# Meanwell_FE.net
KiCad netlist of a schematic drawn in EAGLE
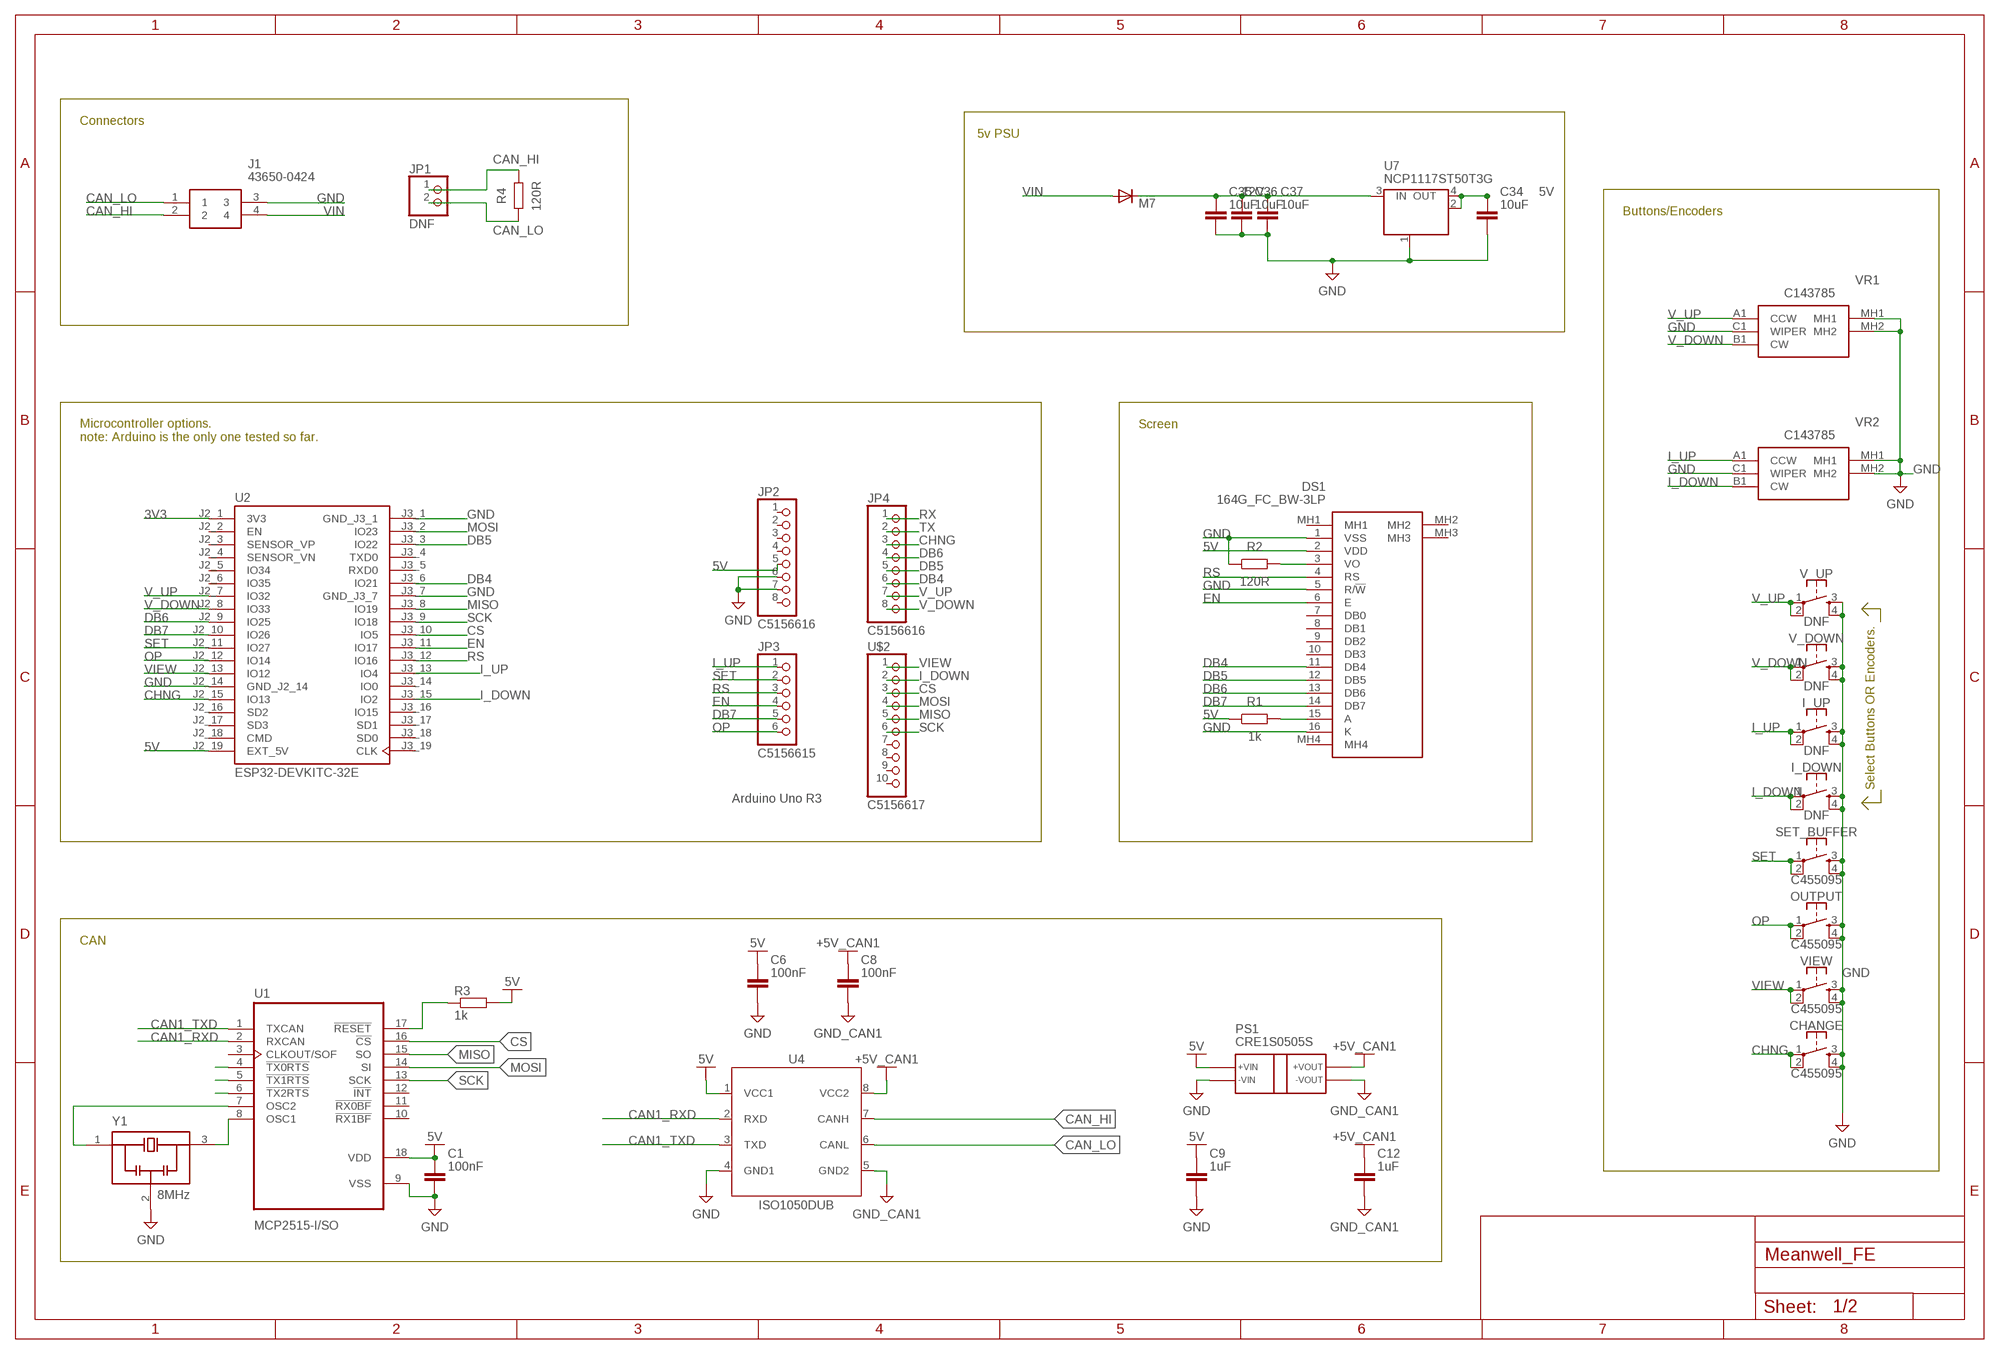
[diagram p0: schematic, sheet 1]
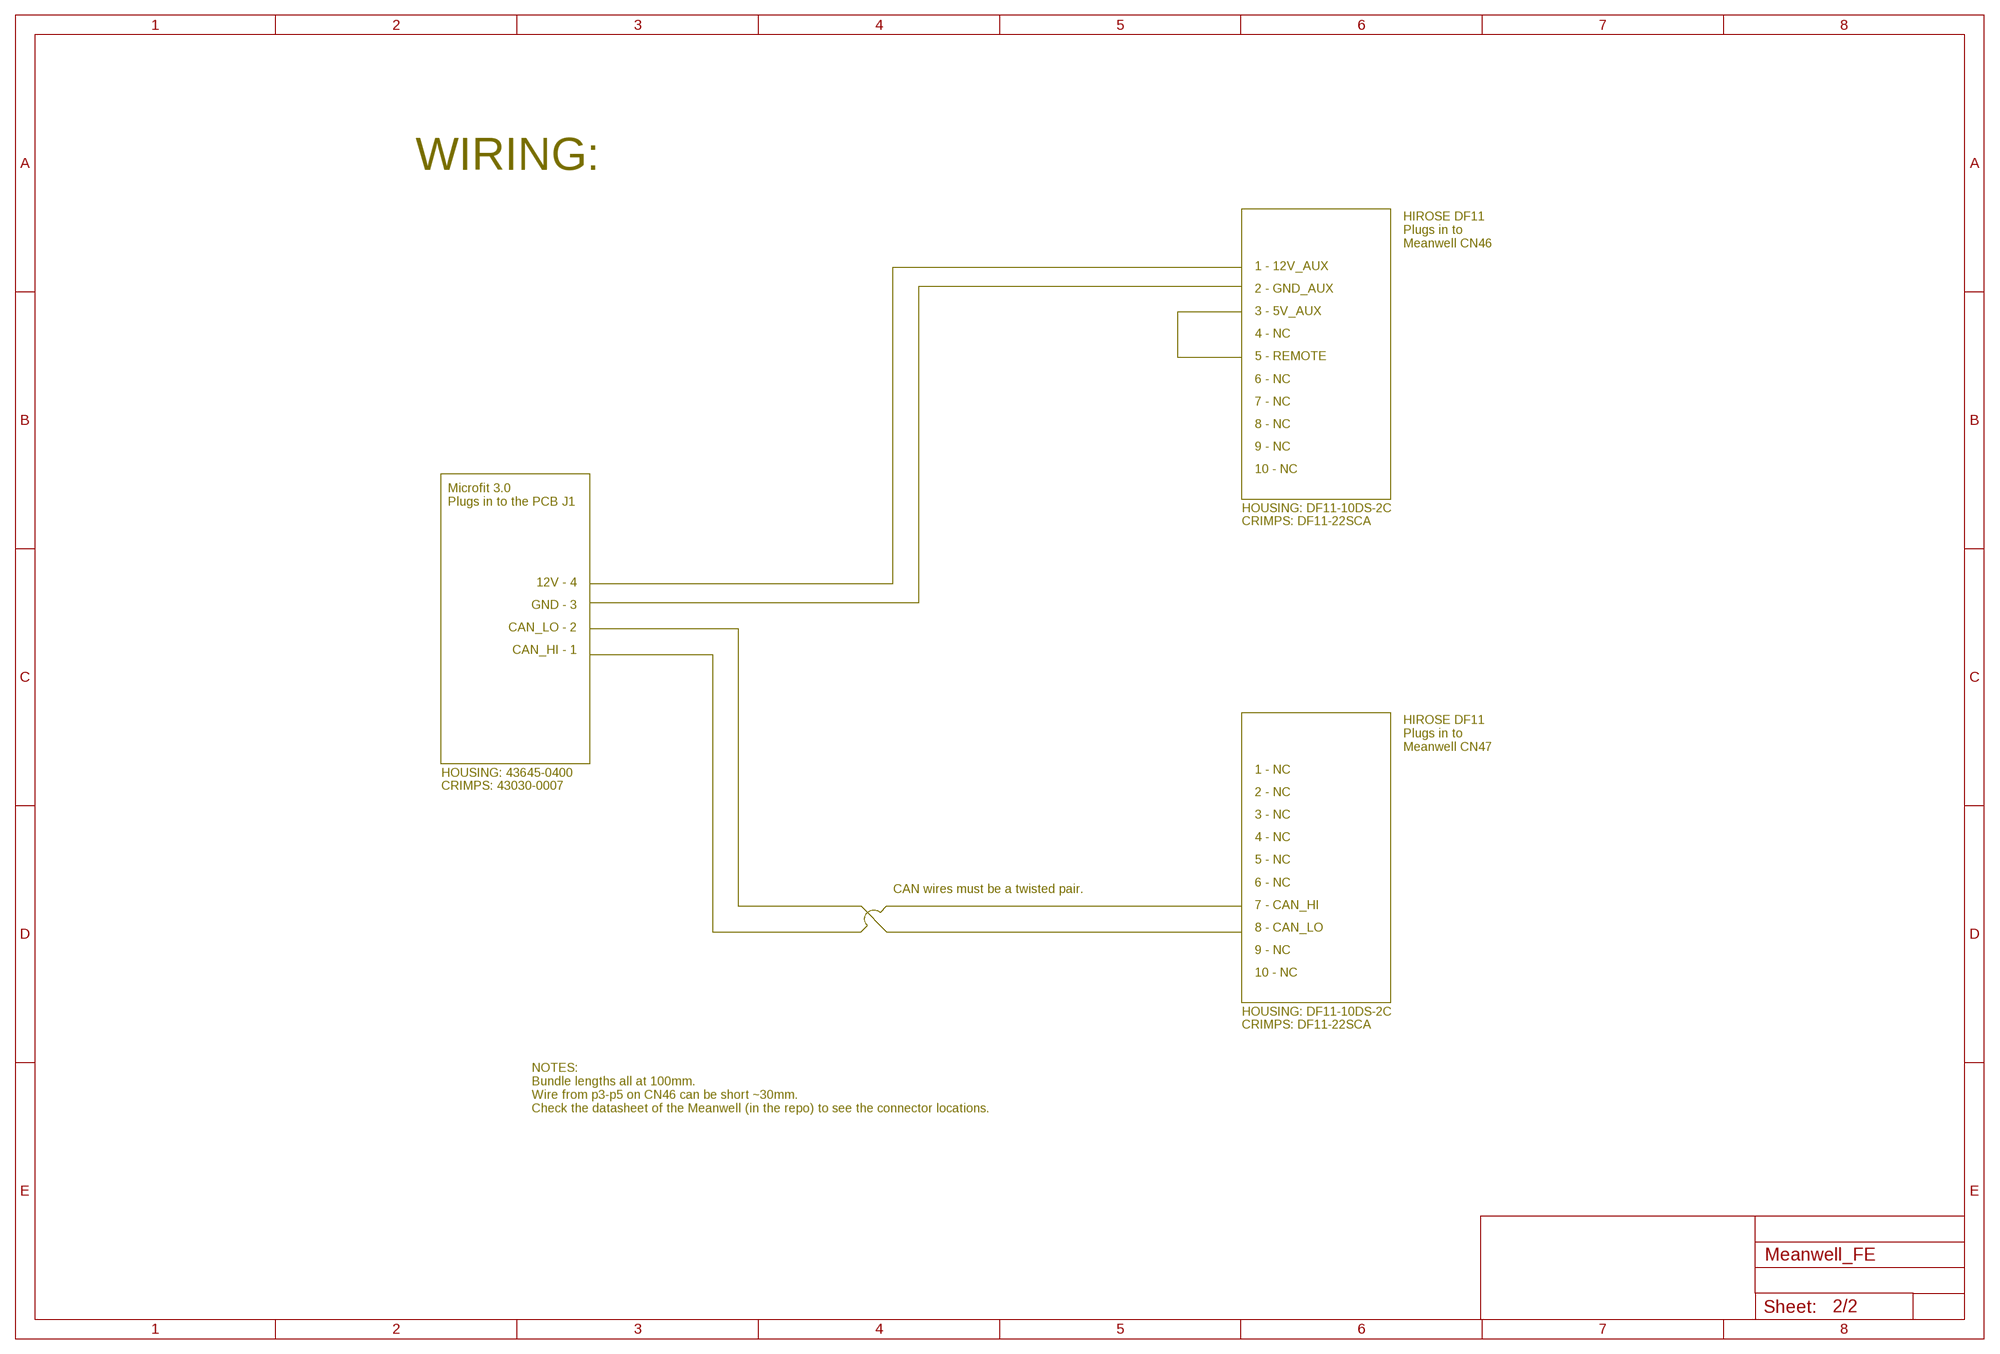
[diagram p1: schematic, sheet 2]

(export (version "E")
  (design (tool "Eeschema 10.0.6"))
  (components
    (comp (ref "C1")
      (value "100nF")
      (footprint "eagle-import:CAPC1608X85")
      (libsource (lib "eagle-import") (part "CCHIP-0603(1608-METRIC)_"))
    )
    (comp (ref "C6")
      (value "100nF")
      (footprint "eagle-import:CAPC1608X85")
      (libsource (lib "eagle-import") (part "CCHIP-0603(1608-METRIC)_"))
    )
    (comp (ref "C8")
      (value "100nF")
      (footprint "eagle-import:CAPC1608X85")
      (libsource (lib "eagle-import") (part "CCHIP-0603(1608-METRIC)_"))
    )
    (comp (ref "C9")
      (value "1uF")
      (footprint "eagle-import:CAPC1608X85")
      (libsource (lib "eagle-import") (part "CCHIP-0603(1608-METRIC)_"))
    )
    (comp (ref "C12")
      (value "1uF")
      (footprint "eagle-import:CAPC1608X85")
      (libsource (lib "eagle-import") (part "CCHIP-0603(1608-METRIC)_"))
    )
    (comp (ref "C34")
      (value "10uF")
      (footprint "eagle-import:CAPC2012X110")
      (libsource (lib "eagle-import") (part "CCHIP-0805(2012-METRIC)_"))
    )
    (comp (ref "C35")
      (value "10uF")
      (footprint "eagle-import:CAPC2012X110")
      (libsource (lib "eagle-import") (part "CCHIP-0805(2012-METRIC)_"))
    )
    (comp (ref "C36")
      (value "10uF")
      (footprint "eagle-import:CAPC2012X110")
      (libsource (lib "eagle-import") (part "CCHIP-0805(2012-METRIC)_"))
    )
    (comp (ref "C37")
      (value "10uF")
      (footprint "eagle-import:CAPC2012X110")
      (libsource (lib "eagle-import") (part "CCHIP-0805(2012-METRIC)_"))
    )
    (comp (ref "CHANGE")
      (value "C455095")
      (footprint "eagle-import:SWITCH-MOMENTARY-PTH-6.5MM")
      (libsource (lib "eagle-import") (part "SWITCH_MOMENTARY"))
    )
    (comp (ref "D1")
      (value "M7")
      (footprint "eagle-import:SMB")
      (libsource (lib "eagle-import") (part "DIODE-SMB"))
    )
    (comp (ref "DS1")
      (value "164G_FC_BW-3LP")
      (footprint "eagle-import:164GFCBW3LP")
      (fields (field (name "MANUFACTURER_PART_NUMBER") "164G FC BW-3LP"))
      (libsource (lib "eagle-import") (part "164G_FC_BW-3LP"))
    )
    (comp (ref "I_DOWN")
      (value "DNF")
      (footprint "eagle-import:SWITCH-MOMENTARY-PTH-6.5MM")
      (libsource (lib "eagle-import") (part "SWITCH_MOMENTARY"))
    )
    (comp (ref "I_UP")
      (value "DNF")
      (footprint "eagle-import:SWITCH-MOMENTARY-PTH-6.5MM")
      (libsource (lib "eagle-import") (part "SWITCH_MOMENTARY"))
    )
    (comp (ref "J1")
      (value "43650-0424")
      (footprint "eagle-import:43650-04YY_242526")
      (fields (field (name "MOUSER_PART_NUMBER") "538-43650-0424"))
      (libsource (lib "eagle-import") (part "43650-0424"))
    )
    (comp (ref "JP1")
      (value "DNF")
      (footprint "eagle-import:1X02")
      (libsource (lib "eagle-import") (part "PINHD-1X2"))
    )
    (comp (ref "JP2")
      (value "C5156616")
      (footprint "eagle-import:1X08-BIG")
      (libsource (lib "eagle-import") (part "PINHD-1X8BIG"))
    )
    (comp (ref "JP3")
      (value "C5156615")
      (footprint "eagle-import:1X06-BIG")
      (libsource (lib "eagle-import") (part "PINHD-1X6B"))
    )
    (comp (ref "JP4")
      (value "C5156616")
      (footprint "eagle-import:1X08-BIG")
      (libsource (lib "eagle-import") (part "PINHD-1X8BIG"))
    )
    (comp (ref "OUTPUT")
      (value "C455095")
      (footprint "eagle-import:SWITCH-MOMENTARY-PTH-6.5MM")
      (libsource (lib "eagle-import") (part "SWITCH_MOMENTARY"))
    )
    (comp (ref "PS1")
      (value "CRE1S0505S")
      (footprint "eagle-import:CRE1(SC)")
      (fields
        (field (name "MANUFACTURER_PART_NUMBER") "CRE1S2405SC")
        (field (name "MOUSER_PART_NUMBER") "580-CRE1S2405SC")
      )
      (libsource (lib "eagle-import") (part "CRE1S0505S"))
    )
    (comp (ref "R1")
      (value "1k")
      (footprint "eagle-import:RESC1608X60")
      (libsource (lib "eagle-import") (part "RCHIP-0603(1608-METRIC)_"))
    )
    (comp (ref "R2")
      (value "120R")
      (footprint "eagle-import:RESC1608X60")
      (libsource (lib "eagle-import") (part "RCHIP-0603(1608-METRIC)_"))
    )
    (comp (ref "R3")
      (value "1k")
      (footprint "eagle-import:RESC1608X60")
      (libsource (lib "eagle-import") (part "RCHIP-0603(1608-METRIC)_"))
    )
    (comp (ref "R4")
      (value "120R")
      (footprint "eagle-import:RESC1608X60")
      (libsource (lib "eagle-import") (part "RCHIP-0603(1608-METRIC)_"))
    )
    (comp (ref "SET_BUFFER")
      (value "C455095")
      (footprint "eagle-import:SWITCH-MOMENTARY-PTH-6.5MM")
      (libsource (lib "eagle-import") (part "SWITCH_MOMENTARY"))
    )
    (comp (ref "U$2")
      (value "C5156617")
      (footprint "eagle-import:1X10-BIG")
      (libsource (lib "eagle-import") (part "PINHD-1X10"))
    )
    (comp (ref "U1")
      (value "MCP2515-I/SO")
      (footprint "eagle-import:SOIC127P1030X265-18N")
      (fields (field (name "MF") "Microchip"))
      (libsource (lib "eagle-import") (part "MCP2515-I/SO"))
    )
    (comp (ref "U2")
      (value "ESP32-DEVKITC-32E")
      (footprint "eagle-import:MODULE_ESP32-DEVKITC-32E")
      (fields (field (name "MANUFACTURER") "Espressif Systems"))
      (libsource (lib "eagle-import") (part "ESP32-DEVKITC-32E"))
    )
    (comp (ref "U4")
      (value "ISO1050DUB")
      (footprint "eagle-import:SOP254P1040X485-8")
      (fields (field (name "MANUFACTURER") "Texas Instruments"))
      (libsource (lib "eagle-import") (part "ISO1050DUB"))
    )
    (comp (ref "U7")
      (value "NCP1117ST50T3G")
      (footprint "eagle-import:SOT223")
      (libsource (lib "eagle-import") (part "MC33269ST-3.3T3"))
    )
    (comp (ref "VIEW")
      (value "C455095")
      (footprint "eagle-import:SWITCH-MOMENTARY-PTH-6.5MM")
      (libsource (lib "eagle-import") (part "SWITCH_MOMENTARY"))
    )
    (comp (ref "VR1")
      (value "C143785")
      (footprint "eagle-import:PEC12R4215FN0024")
      (fields
        (field (name "MANUFACTURER_PART_NUMBER") "PEC12R-4215F-N0024")
        (field (name "MOUSER_PART_NUMBER") "652-PEC12R4215FN0024")
      )
      (libsource (lib "eagle-import") (part "PEC12R-4215F-N0024"))
    )
    (comp (ref "VR2")
      (value "C143785")
      (footprint "eagle-import:PEC12R4215FN0024")
      (fields
        (field (name "MANUFACTURER_PART_NUMBER") "PEC12R-4215F-N0024")
        (field (name "MOUSER_PART_NUMBER") "652-PEC12R4215FN0024")
      )
      (libsource (lib "eagle-import") (part "PEC12R-4215F-N0024"))
    )
    (comp (ref "V_DOWN")
      (value "DNF")
      (footprint "eagle-import:SWITCH-MOMENTARY-PTH-6.5MM")
      (libsource (lib "eagle-import") (part "SWITCH_MOMENTARY"))
    )
    (comp (ref "V_UP")
      (value "DNF")
      (footprint "eagle-import:SWITCH-MOMENTARY-PTH-6.5MM")
      (libsource (lib "eagle-import") (part "SWITCH_MOMENTARY"))
    )
    (comp (ref "Y1")
      (value "8MHz")
      (footprint "eagle-import:OSC_CSTNE8M00GH5C000R0")
      (fields (field (name "MF") "Murata Electronics") (field (name "MP") "CSTNE8M00GH5C000R0"))
      (libsource (lib "eagle-import") (part "CSTNE8M00GH5C000R0"))
    )
  )
  (nets
    (net (code "1") (name "+5V_CAN1") (class "Default")
      (node (ref "C12") (pin "1") (pinfunction "1_1") (pintype "passive"))
      (node (ref "C8") (pin "1") (pinfunction "1_1") (pintype "passive"))
      (node (ref "PS1") (pin "4") (pinfunction "+VOUT_4") (pintype "bidirectional"))
      (node (ref "U4") (pin "8") (pinfunction "VCC2_8") (pintype "power_in"))
    )
    (net (code "2") (name "3V3") (class "Default")
      (node (ref "U2") (pin "J2_1") (pinfunction "3V3_J2_1") (pintype "power_in"))
    )
    (net (code "3") (name "5V") (class "Default")
      (node (ref "C1") (pin "1") (pinfunction "1_1") (pintype "passive"))
      (node (ref "C34") (pin "1") (pinfunction "1_1") (pintype "passive"))
      (node (ref "C6") (pin "1") (pinfunction "1_1") (pintype "passive"))
      (node (ref "C9") (pin "1") (pinfunction "1_1") (pintype "passive"))
      (node (ref "DS1") (pin "2") (pinfunction "VDD_2") (pintype "bidirectional"))
      (node (ref "JP2") (pin "5") (pinfunction "5_5") (pintype "passive"))
      (node (ref "PS1") (pin "2") (pinfunction "+VIN_2") (pintype "bidirectional"))
      (node (ref "R1") (pin "1") (pinfunction "1_1") (pintype "passive"))
      (node (ref "R3") (pin "2") (pinfunction "2_2") (pintype "passive"))
      (node (ref "U1") (pin "18") (pinfunction "VDD_18") (pintype "power_in"))
      (node (ref "U2") (pin "J2_19") (pinfunction "EXT_5V_J2_19") (pintype "power_in"))
      (node (ref "U4") (pin "1") (pinfunction "VCC1_1") (pintype "power_in"))
      (node (ref "U7") (pin "2") (pinfunction "OUT_2") (pintype "passive"))
      (node (ref "U7") (pin "4") (pinfunction "OUT_4") (pintype "passive"))
    )
    (net (code "4") (name "12V") (class "Default")
      (node (ref "C35") (pin "1") (pinfunction "1_1") (pintype "passive"))
      (node (ref "C36") (pin "1") (pinfunction "1_1") (pintype "passive"))
      (node (ref "C37") (pin "1") (pinfunction "1_1") (pintype "passive"))
      (node (ref "D1") (pin "C") (pinfunction "C_C") (pintype "passive"))
      (node (ref "U7") (pin "3") (pinfunction "IN_3") (pintype "input"))
    )
    (net (code "5") (name "CAN1_RXD") (class "Default")
      (node (ref "U1") (pin "2") (pinfunction "RXCAN_2") (pintype "input"))
      (node (ref "U4") (pin "2") (pinfunction "RXD_2") (pintype "output"))
    )
    (net (code "6") (name "CAN1_TXD") (class "Default")
      (node (ref "U1") (pin "1") (pinfunction "TXCAN_1") (pintype "output"))
      (node (ref "U4") (pin "3") (pinfunction "TXD_3") (pintype "input"))
    )
    (net (code "7") (name "CAN_HI") (class "Default")
      (node (ref "J1") (pin "2") (pinfunction "2_2") (pintype "bidirectional"))
      (node (ref "JP1") (pin "1") (pinfunction "1_1") (pintype "passive"))
      (node (ref "R4") (pin "2") (pinfunction "2_2") (pintype "passive"))
      (node (ref "U4") (pin "7") (pinfunction "CANH_7") (pintype "bidirectional"))
    )
    (net (code "8") (name "CAN_LO") (class "Default")
      (node (ref "J1") (pin "1") (pinfunction "1_1") (pintype "bidirectional"))
      (node (ref "JP1") (pin "2") (pinfunction "2_2") (pintype "passive"))
      (node (ref "R4") (pin "1") (pinfunction "1_1") (pintype "passive"))
      (node (ref "U4") (pin "6") (pinfunction "CANL_6") (pintype "bidirectional"))
    )
    (net (code "9") (name "CHNG") (class "Default")
      (node (ref "CHANGE") (pin "1") (pinfunction "1_1") (pintype "passive"))
      (node (ref "CHANGE") (pin "2") (pinfunction "2_2") (pintype "passive"))
      (node (ref "JP4") (pin "3") (pinfunction "3_3") (pintype "passive"))
      (node (ref "U2") (pin "J2_15") (pinfunction "IO13_J2_15") (pintype "bidirectional"))
    )
    (net (code "10") (name "CS") (class "Default")
      (node (ref "U$2") (pin "3") (pinfunction "3_3") (pintype "passive"))
      (node (ref "U1") (pin "16") (pinfunction "~{CS}_16") (pintype "input"))
      (node (ref "U2") (pin "J3_10") (pinfunction "IO5_J3_10") (pintype "bidirectional"))
    )
    (net (code "11") (name "DB4") (class "Default")
      (node (ref "DS1") (pin "11") (pinfunction "DB4_11") (pintype "bidirectional"))
      (node (ref "JP4") (pin "6") (pinfunction "6_6") (pintype "passive"))
      (node (ref "U2") (pin "J3_6") (pinfunction "IO21_J3_6") (pintype "bidirectional"))
    )
    (net (code "12") (name "DB5") (class "Default")
      (node (ref "DS1") (pin "12") (pinfunction "DB5_12") (pintype "bidirectional"))
      (node (ref "JP4") (pin "5") (pinfunction "5_5") (pintype "passive"))
      (node (ref "U2") (pin "J3_3") (pinfunction "IO22_J3_3") (pintype "bidirectional"))
    )
    (net (code "13") (name "DB6") (class "Default")
      (node (ref "DS1") (pin "13") (pinfunction "DB6_13") (pintype "bidirectional"))
      (node (ref "JP4") (pin "4") (pinfunction "4_4") (pintype "passive"))
      (node (ref "U2") (pin "J2_9") (pinfunction "IO25_J2_9") (pintype "bidirectional"))
    )
    (net (code "14") (name "DB7") (class "Default")
      (node (ref "DS1") (pin "14") (pinfunction "DB7_14") (pintype "bidirectional"))
      (node (ref "JP3") (pin "5") (pinfunction "5_5") (pintype "passive"))
      (node (ref "U2") (pin "J2_10") (pinfunction "IO26_J2_10") (pintype "bidirectional"))
    )
    (net (code "15") (name "EN") (class "Default")
      (node (ref "DS1") (pin "6") (pinfunction "E_6") (pintype "bidirectional"))
      (node (ref "JP3") (pin "4") (pinfunction "4_4") (pintype "passive"))
      (node (ref "U2") (pin "J3_11") (pinfunction "IO17_J3_11") (pintype "bidirectional"))
    )
    (net (code "16") (name "GND") (class "Default")
      (node (ref "C1") (pin "2") (pinfunction "2_2") (pintype "passive"))
      (node (ref "C34") (pin "2") (pinfunction "2_2") (pintype "passive"))
      (node (ref "C35") (pin "2") (pinfunction "2_2") (pintype "passive"))
      (node (ref "C36") (pin "2") (pinfunction "2_2") (pintype "passive"))
      (node (ref "C37") (pin "2") (pinfunction "2_2") (pintype "passive"))
      (node (ref "C6") (pin "2") (pinfunction "2_2") (pintype "passive"))
      (node (ref "C9") (pin "2") (pinfunction "2_2") (pintype "passive"))
      (node (ref "CHANGE") (pin "3") (pinfunction "3_3") (pintype "passive"))
      (node (ref "CHANGE") (pin "4") (pinfunction "4_4") (pintype "passive"))
      (node (ref "DS1") (pin "1") (pinfunction "VSS_1") (pintype "bidirectional"))
      (node (ref "DS1") (pin "16") (pinfunction "K_16") (pintype "bidirectional"))
      (node (ref "DS1") (pin "5") (pinfunction "R/~{W}_5") (pintype "bidirectional"))
      (node (ref "I_DOWN") (pin "3") (pinfunction "3_3") (pintype "passive"))
      (node (ref "I_DOWN") (pin "4") (pinfunction "4_4") (pintype "passive"))
      (node (ref "I_UP") (pin "3") (pinfunction "3_3") (pintype "passive"))
      (node (ref "I_UP") (pin "4") (pinfunction "4_4") (pintype "passive"))
      (node (ref "J1") (pin "3") (pinfunction "3_3") (pintype "bidirectional"))
      (node (ref "JP2") (pin "6") (pinfunction "6_6") (pintype "passive"))
      (node (ref "JP2") (pin "7") (pinfunction "7_7") (pintype "passive"))
      (node (ref "OUTPUT") (pin "3") (pinfunction "3_3") (pintype "passive"))
      (node (ref "OUTPUT") (pin "4") (pinfunction "4_4") (pintype "passive"))
      (node (ref "PS1") (pin "1") (pinfunction "-VIN_1") (pintype "bidirectional"))
      (node (ref "R2") (pin "1") (pinfunction "1_1") (pintype "passive"))
      (node (ref "SET_BUFFER") (pin "3") (pinfunction "3_3") (pintype "passive"))
      (node (ref "SET_BUFFER") (pin "4") (pinfunction "4_4") (pintype "passive"))
      (node (ref "U1") (pin "9") (pinfunction "VSS_9") (pintype "power_in"))
      (node (ref "U2") (pin "J2_14") (pinfunction "GND_J2_14_J2_14") (pintype "power_in"))
      (node (ref "U2") (pin "J3_1") (pinfunction "GND_J3_1_J3_1") (pintype "power_in"))
      (node (ref "U2") (pin "J3_7") (pinfunction "GND_J3_7_J3_7") (pintype "power_in"))
      (node (ref "U4") (pin "4") (pinfunction "GND1_4") (pintype "power_in"))
      (node (ref "U7") (pin "1") (pinfunction "GND/ADJ_1") (pintype "input"))
      (node (ref "VIEW") (pin "3") (pinfunction "3_3") (pintype "passive"))
      (node (ref "VIEW") (pin "4") (pinfunction "4_4") (pintype "passive"))
      (node (ref "VR1") (pin "C1") (pinfunction "WIPER_C1") (pintype "bidirectional"))
      (node (ref "VR1") (pin "MH1") (pinfunction "MH1_MH1") (pintype "bidirectional"))
      (node (ref "VR1") (pin "MH2") (pinfunction "MH2_MH2") (pintype "bidirectional"))
      (node (ref "VR2") (pin "C1") (pinfunction "WIPER_C1") (pintype "bidirectional"))
      (node (ref "VR2") (pin "MH1") (pinfunction "MH1_MH1") (pintype "bidirectional"))
      (node (ref "VR2") (pin "MH2") (pinfunction "MH2_MH2") (pintype "bidirectional"))
      (node (ref "V_DOWN") (pin "3") (pinfunction "3_3") (pintype "passive"))
      (node (ref "V_DOWN") (pin "4") (pinfunction "4_4") (pintype "passive"))
      (node (ref "V_UP") (pin "3") (pinfunction "3_3") (pintype "passive"))
      (node (ref "V_UP") (pin "4") (pinfunction "4_4") (pintype "passive"))
      (node (ref "Y1") (pin "2") (pinfunction "GND_2") (pintype "power_in"))
    )
    (net (code "17") (name "GND_CAN1") (class "Default")
      (node (ref "C12") (pin "2") (pinfunction "2_2") (pintype "passive"))
      (node (ref "C8") (pin "2") (pinfunction "2_2") (pintype "passive"))
      (node (ref "PS1") (pin "3") (pinfunction "-VOUT_3") (pintype "bidirectional"))
      (node (ref "U4") (pin "5") (pinfunction "GND2_5") (pintype "power_in"))
    )
    (net (code "18") (name "I_DOWN") (class "Default")
      (node (ref "I_DOWN") (pin "1") (pinfunction "1_1") (pintype "passive"))
      (node (ref "I_DOWN") (pin "2") (pinfunction "2_2") (pintype "passive"))
      (node (ref "U$2") (pin "2") (pinfunction "2_2") (pintype "passive"))
      (node (ref "U2") (pin "J3_15") (pinfunction "IO2_J3_15") (pintype "bidirectional"))
      (node (ref "VR2") (pin "B1") (pinfunction "CW_B1") (pintype "bidirectional"))
    )
    (net (code "19") (name "I_UP") (class "Default")
      (node (ref "I_UP") (pin "1") (pinfunction "1_1") (pintype "passive"))
      (node (ref "I_UP") (pin "2") (pinfunction "2_2") (pintype "passive"))
      (node (ref "JP3") (pin "1") (pinfunction "1_1") (pintype "passive"))
      (node (ref "U2") (pin "J3_13") (pinfunction "IO4_J3_13") (pintype "bidirectional"))
      (node (ref "VR2") (pin "A1") (pinfunction "CCW_A1") (pintype "bidirectional"))
    )
    (net (code "20") (name "MISO") (class "Default")
      (node (ref "U$2") (pin "5") (pinfunction "5_5") (pintype "passive"))
      (node (ref "U1") (pin "15") (pinfunction "SO_15") (pintype "output"))
      (node (ref "U2") (pin "J3_8") (pinfunction "IO19_J3_8") (pintype "bidirectional"))
    )
    (net (code "21") (name "MOSI") (class "Default")
      (node (ref "U$2") (pin "4") (pinfunction "4_4") (pintype "passive"))
      (node (ref "U1") (pin "14") (pinfunction "SI_14") (pintype "input"))
      (node (ref "U2") (pin "J3_2") (pinfunction "IO23_J3_2") (pintype "bidirectional"))
    )
    (net (code "22") (name "Net-(DS1-A)") (class "Default")
      (node (ref "DS1") (pin "15") (pinfunction "A_15") (pintype "bidirectional"))
      (node (ref "R1") (pin "2") (pinfunction "2_2") (pintype "passive"))
    )
    (net (code "23") (name "Net-(DS1-VO)") (class "Default")
      (node (ref "DS1") (pin "3") (pinfunction "VO_3") (pintype "bidirectional"))
      (node (ref "R2") (pin "2") (pinfunction "2_2") (pintype "passive"))
    )
    (net (code "24") (name "Net-(U1-OSC1)") (class "Default")
      (node (ref "U1") (pin "8") (pinfunction "OSC1_8") (pintype "input"))
      (node (ref "Y1") (pin "3") (pinfunction "OUT_3") (pintype "output"))
    )
    (net (code "25") (name "Net-(U1-OSC2)") (class "Default")
      (node (ref "U1") (pin "7") (pinfunction "OSC2_7") (pintype "output"))
      (node (ref "Y1") (pin "1") (pinfunction "IN_1") (pintype "input"))
    )
    (net (code "26") (name "Net-(U1-~{RESET})") (class "Default")
      (node (ref "R3") (pin "1") (pinfunction "1_1") (pintype "passive"))
      (node (ref "U1") (pin "17") (pinfunction "~{RESET}_17") (pintype "input"))
    )
    (net (code "27") (name "OP") (class "Default")
      (node (ref "JP3") (pin "6") (pinfunction "6_6") (pintype "passive"))
      (node (ref "OUTPUT") (pin "1") (pinfunction "1_1") (pintype "passive"))
      (node (ref "OUTPUT") (pin "2") (pinfunction "2_2") (pintype "passive"))
      (node (ref "U2") (pin "J2_12") (pinfunction "IO14_J2_12") (pintype "bidirectional"))
    )
    (net (code "28") (name "RS") (class "Default")
      (node (ref "DS1") (pin "4") (pinfunction "RS_4") (pintype "bidirectional"))
      (node (ref "JP3") (pin "3") (pinfunction "3_3") (pintype "passive"))
      (node (ref "U2") (pin "J3_12") (pinfunction "IO16_J3_12") (pintype "bidirectional"))
    )
    (net (code "29") (name "RX") (class "Default")
      (node (ref "JP4") (pin "1") (pinfunction "1_1") (pintype "passive"))
    )
    (net (code "30") (name "SCK") (class "Default")
      (node (ref "U$2") (pin "6") (pinfunction "6_6") (pintype "passive"))
      (node (ref "U1") (pin "13") (pinfunction "SCK_13") (pintype "input"))
      (node (ref "U2") (pin "J3_9") (pinfunction "IO18_J3_9") (pintype "bidirectional"))
    )
    (net (code "31") (name "SET") (class "Default")
      (node (ref "JP3") (pin "2") (pinfunction "2_2") (pintype "passive"))
      (node (ref "SET_BUFFER") (pin "1") (pinfunction "1_1") (pintype "passive"))
      (node (ref "SET_BUFFER") (pin "2") (pinfunction "2_2") (pintype "passive"))
      (node (ref "U2") (pin "J2_11") (pinfunction "IO27_J2_11") (pintype "bidirectional"))
    )
    (net (code "32") (name "TX") (class "Default")
      (node (ref "JP4") (pin "2") (pinfunction "2_2") (pintype "passive"))
    )
    (net (code "33") (name "VIEW") (class "Default")
      (node (ref "U$2") (pin "1") (pinfunction "1_1") (pintype "passive"))
      (node (ref "U2") (pin "J2_13") (pinfunction "IO12_J2_13") (pintype "bidirectional"))
      (node (ref "VIEW") (pin "1") (pinfunction "1_1") (pintype "passive"))
      (node (ref "VIEW") (pin "2") (pinfunction "2_2") (pintype "passive"))
    )
    (net (code "34") (name "VIN") (class "Default")
      (node (ref "D1") (pin "A") (pinfunction "A_A") (pintype "passive"))
      (node (ref "J1") (pin "4") (pinfunction "4_4") (pintype "bidirectional"))
    )
    (net (code "35") (name "V_DOWN") (class "Default")
      (node (ref "JP4") (pin "8") (pinfunction "8_8") (pintype "passive"))
      (node (ref "U2") (pin "J2_8") (pinfunction "IO33_J2_8") (pintype "bidirectional"))
      (node (ref "VR1") (pin "B1") (pinfunction "CW_B1") (pintype "bidirectional"))
      (node (ref "V_DOWN") (pin "1") (pinfunction "1_1") (pintype "passive"))
      (node (ref "V_DOWN") (pin "2") (pinfunction "2_2") (pintype "passive"))
    )
    (net (code "36") (name "V_UP") (class "Default")
      (node (ref "JP4") (pin "7") (pinfunction "7_7") (pintype "passive"))
      (node (ref "U2") (pin "J2_7") (pinfunction "IO32_J2_7") (pintype "bidirectional"))
      (node (ref "VR1") (pin "A1") (pinfunction "CCW_A1") (pintype "bidirectional"))
      (node (ref "V_UP") (pin "1") (pinfunction "1_1") (pintype "passive"))
      (node (ref "V_UP") (pin "2") (pinfunction "2_2") (pintype "passive"))
    )
    (net (code "37") (name "unconnected-(DS1-DB0-Pad7)") (class "Default")
      (node (ref "DS1") (pin "7") (pinfunction "DB0_7") (pintype "bidirectional"))
    )
    (net (code "38") (name "unconnected-(DS1-DB1-Pad8)") (class "Default")
      (node (ref "DS1") (pin "8") (pinfunction "DB1_8") (pintype "bidirectional"))
    )
    (net (code "39") (name "unconnected-(DS1-DB2-Pad9)") (class "Default")
      (node (ref "DS1") (pin "9") (pinfunction "DB2_9") (pintype "bidirectional"))
    )
    (net (code "40") (name "unconnected-(DS1-DB3-Pad10)") (class "Default")
      (node (ref "DS1") (pin "10") (pinfunction "DB3_10") (pintype "bidirectional"))
    )
    (net (code "41") (name "unconnected-(DS1-PadMH1)") (class "Default")
      (node (ref "DS1") (pin "MH1") (pinfunction "MH1_MH1") (pintype "bidirectional"))
    )
    (net (code "42") (name "unconnected-(DS1-PadMH2)") (class "Default")
      (node (ref "DS1") (pin "MH2") (pinfunction "MH2_MH2") (pintype "bidirectional"))
    )
    (net (code "43") (name "unconnected-(DS1-PadMH3)") (class "Default")
      (node (ref "DS1") (pin "MH3") (pinfunction "MH3_MH3") (pintype "bidirectional"))
    )
    (net (code "44") (name "unconnected-(DS1-PadMH4)") (class "Default")
      (node (ref "DS1") (pin "MH4") (pinfunction "MH4_MH4") (pintype "bidirectional"))
    )
    (net (code "45") (name "unconnected-(JP2-Pad1)") (class "Default")
      (node (ref "JP2") (pin "1") (pinfunction "1_1") (pintype "passive"))
    )
    (net (code "46") (name "unconnected-(JP2-Pad2)") (class "Default")
      (node (ref "JP2") (pin "2") (pinfunction "2_2") (pintype "passive"))
    )
    (net (code "47") (name "unconnected-(JP2-Pad3)") (class "Default")
      (node (ref "JP2") (pin "3") (pinfunction "3_3") (pintype "passive"))
    )
    (net (code "48") (name "unconnected-(JP2-Pad4)") (class "Default")
      (node (ref "JP2") (pin "4") (pinfunction "4_4") (pintype "passive"))
    )
    (net (code "49") (name "unconnected-(JP2-Pad8)") (class "Default")
      (node (ref "JP2") (pin "8") (pinfunction "8_8") (pintype "passive"))
    )
    (net (code "50") (name "unconnected-(U$2-Pad7)") (class "Default")
      (node (ref "U$2") (pin "7") (pinfunction "7_7") (pintype "passive"))
    )
    (net (code "51") (name "unconnected-(U$2-Pad8)") (class "Default")
      (node (ref "U$2") (pin "8") (pinfunction "8_8") (pintype "passive"))
    )
    (net (code "52") (name "unconnected-(U$2-Pad9)") (class "Default")
      (node (ref "U$2") (pin "9") (pinfunction "9_9") (pintype "passive"))
    )
    (net (code "53") (name "unconnected-(U$2-Pad10)") (class "Default")
      (node (ref "U$2") (pin "10") (pinfunction "10_10") (pintype "passive"))
    )
    (net (code "54") (name "unconnected-(U1-CLKOUT{slash}SOF-Pad3)") (class "Default")
      (node (ref "U1") (pin "3") (pinfunction "CLKOUT/SOF_3") (pintype "output"))
    )
    (net (code "55") (name "unconnected-(U1-~{INT}-Pad12)") (class "Default")
      (node (ref "U1") (pin "12") (pinfunction "~{INT}_12") (pintype "output"))
    )
    (net (code "56") (name "unconnected-(U1-~{RX0BF}-Pad11)") (class "Default")
      (node (ref "U1") (pin "11") (pinfunction "~{RX0BF}_11") (pintype "output"))
    )
    (net (code "57") (name "unconnected-(U1-~{RX1BF}-Pad10)") (class "Default")
      (node (ref "U1") (pin "10") (pinfunction "~{RX1BF}_10") (pintype "output"))
    )
    (net (code "58") (name "unconnected-(U1-~{TX0RTS}-Pad4)") (class "Default")
      (node (ref "U1") (pin "4") (pinfunction "~{TX0RTS}_4") (pintype "bidirectional"))
    )
    (net (code "59") (name "unconnected-(U1-~{TX1RTS}-Pad5)") (class "Default")
      (node (ref "U1") (pin "5") (pinfunction "~{TX1RTS}_5") (pintype "bidirectional"))
    )
    (net (code "60") (name "unconnected-(U1-~{TX2RTS}-Pad6)") (class "Default")
      (node (ref "U1") (pin "6") (pinfunction "~{TX2RTS}_6") (pintype "bidirectional"))
    )
    (net (code "61") (name "unconnected-(U2-CLK-PadJ3_19)") (class "Default")
      (node (ref "U2") (pin "J3_19") (pinfunction "CLK_J3_19") (pintype "bidirectional"))
    )
    (net (code "62") (name "unconnected-(U2-CMD-PadJ2_18)") (class "Default")
      (node (ref "U2") (pin "J2_18") (pinfunction "CMD_J2_18") (pintype "bidirectional"))
    )
    (net (code "63") (name "unconnected-(U2-EN-PadJ2_2)") (class "Default")
      (node (ref "U2") (pin "J2_2") (pinfunction "EN_J2_2") (pintype "input"))
    )
    (net (code "64") (name "unconnected-(U2-IO0-PadJ3_14)") (class "Default")
      (node (ref "U2") (pin "J3_14") (pinfunction "IO0_J3_14") (pintype "bidirectional"))
    )
    (net (code "65") (name "unconnected-(U2-IO15-PadJ3_16)") (class "Default")
      (node (ref "U2") (pin "J3_16") (pinfunction "IO15_J3_16") (pintype "bidirectional"))
    )
    (net (code "66") (name "unconnected-(U2-IO34-PadJ2_5)") (class "Default")
      (node (ref "U2") (pin "J2_5") (pinfunction "IO34_J2_5") (pintype "bidirectional"))
    )
    (net (code "67") (name "unconnected-(U2-IO35-PadJ2_6)") (class "Default")
      (node (ref "U2") (pin "J2_6") (pinfunction "IO35_J2_6") (pintype "bidirectional"))
    )
    (net (code "68") (name "unconnected-(U2-RXD0-PadJ3_5)") (class "Default")
      (node (ref "U2") (pin "J3_5") (pinfunction "RXD0_J3_5") (pintype "bidirectional"))
    )
    (net (code "69") (name "unconnected-(U2-SD0-PadJ3_18)") (class "Default")
      (node (ref "U2") (pin "J3_18") (pinfunction "SD0_J3_18") (pintype "bidirectional"))
    )
    (net (code "70") (name "unconnected-(U2-SD1-PadJ3_17)") (class "Default")
      (node (ref "U2") (pin "J3_17") (pinfunction "SD1_J3_17") (pintype "bidirectional"))
    )
    (net (code "71") (name "unconnected-(U2-SD2-PadJ2_16)") (class "Default")
      (node (ref "U2") (pin "J2_16") (pinfunction "SD2_J2_16") (pintype "bidirectional"))
    )
    (net (code "72") (name "unconnected-(U2-SD3-PadJ2_17)") (class "Default")
      (node (ref "U2") (pin "J2_17") (pinfunction "SD3_J2_17") (pintype "bidirectional"))
    )
    (net (code "73") (name "unconnected-(U2-SENSOR_VN-PadJ2_4)") (class "Default")
      (node (ref "U2") (pin "J2_4") (pinfunction "SENSOR_VN_J2_4") (pintype "bidirectional"))
    )
    (net (code "74") (name "unconnected-(U2-SENSOR_VP-PadJ2_3)") (class "Default")
      (node (ref "U2") (pin "J2_3") (pinfunction "SENSOR_VP_J2_3") (pintype "bidirectional"))
    )
    (net (code "75") (name "unconnected-(U2-TXD0-PadJ3_4)") (class "Default")
      (node (ref "U2") (pin "J3_4") (pinfunction "TXD0_J3_4") (pintype "bidirectional"))
    )
  )
)
